# breakout.net
KiCad netlist of a schematic drawn in EAGLE
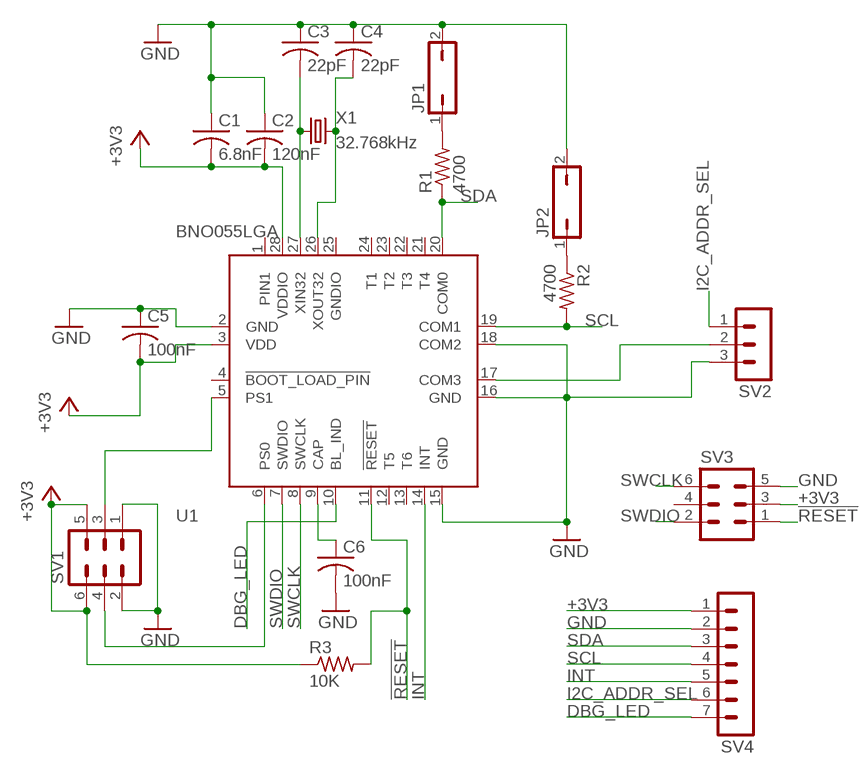
[diagram p0: schematic, sheet 1]

(export (version "E")
  (design (tool "Eeschema 10.0.6"))
  (components
    (comp (ref "C1")
      (value "6.8nF")
      (footprint "eagle-import:C0805")
      (libsource (lib "eagle-import") (part "C-USC0805"))
    )
    (comp (ref "C2")
      (value "120nF")
      (footprint "eagle-import:C0805")
      (libsource (lib "eagle-import") (part "C-USC0805"))
    )
    (comp (ref "C3")
      (value "22pF")
      (footprint "eagle-import:C0805")
      (libsource (lib "eagle-import") (part "C-USC0805"))
    )
    (comp (ref "C4")
      (value "22pF")
      (footprint "eagle-import:C0805")
      (libsource (lib "eagle-import") (part "C-USC0805"))
    )
    (comp (ref "C5")
      (value "100nF")
      (footprint "eagle-import:C0805")
      (libsource (lib "eagle-import") (part "C-USC0805"))
    )
    (comp (ref "C6")
      (value "100nF")
      (footprint "eagle-import:C0805")
      (libsource (lib "eagle-import") (part "C-USC0805"))
    )
    (comp (ref "JP1")
      (value "JP1Q")
      (footprint "eagle-import:JP1")
      (libsource (lib "eagle-import") (part "JP1Q"))
    )
    (comp (ref "JP2")
      (value "JP1Q")
      (footprint "eagle-import:JP1")
      (libsource (lib "eagle-import") (part "JP1Q"))
    )
    (comp (ref "R1")
      (value "4700")
      (footprint "eagle-import:R0805")
      (libsource (lib "eagle-import") (part "R-US_R0805"))
    )
    (comp (ref "R2")
      (value "4700")
      (footprint "eagle-import:R0805")
      (libsource (lib "eagle-import") (part "R-US_R0805"))
    )
    (comp (ref "R3")
      (value "10K")
      (footprint "eagle-import:R0805")
      (libsource (lib "eagle-import") (part "R-US_R0805"))
    )
    (comp (ref "SV1")
      (value "MA03-2")
      (footprint "eagle-import:MA03-2")
      (libsource (lib "eagle-import") (part "MA03-2"))
    )
    (comp (ref "SV2")
      (value "MA03-1")
      (footprint "eagle-import:MA03-1")
      (libsource (lib "eagle-import") (part "MA03-1"))
    )
    (comp (ref "SV3")
      (value "MA03-2")
      (footprint "eagle-import:MA03-2")
      (libsource (lib "eagle-import") (part "MA03-2"))
    )
    (comp (ref "SV4")
      (value "MA07-1")
      (footprint "eagle-import:MA07-1")
      (libsource (lib "eagle-import") (part "MA07-1"))
    )
    (comp (ref "U1")
      (value "BNO055LGA")
      (footprint "eagle-import:LGA28_BOSCH")
      (libsource (lib "eagle-import") (part "BNO055LGA"))
    )
    (comp (ref "X1")
      (value "32.768kHz")
      (footprint "eagle-import:WATCH-3X8")
      (libsource (lib "eagle-import") (part "CRYSTALS-NOGND-WATCH-3X8"))
    )
  )
  (nets
    (net (code "1") (name "+3V3") (class "Default")
      (node (ref "C1") (pin "2") (pinfunction "2_2") (pintype "passive"))
      (node (ref "C2") (pin "2") (pinfunction "2_2") (pintype "passive"))
      (node (ref "C5") (pin "2") (pinfunction "2_2") (pintype "passive"))
      (node (ref "R3") (pin "1") (pinfunction "1_1") (pintype "passive"))
      (node (ref "SV1") (pin "5") (pinfunction "5_5") (pintype "passive"))
      (node (ref "SV1") (pin "6") (pinfunction "6_6") (pintype "passive"))
      (node (ref "SV3") (pin "3") (pinfunction "3_3") (pintype "passive"))
      (node (ref "SV4") (pin "1") (pinfunction "1_1") (pintype "passive"))
      (node (ref "U1") (pin "28") (pinfunction "VDDIO_28") (pintype "power_in"))
      (node (ref "U1") (pin "3") (pinfunction "VDD_3") (pintype "power_in"))
    )
    (net (code "2") (name "/DBG_LED") (class "Default")
      (node (ref "SV4") (pin "7") (pinfunction "7_7") (pintype "passive"))
      (node (ref "U1") (pin "10") (pinfunction "BL_IND_10") (pintype "output"))
    )
    (net (code "3") (name "/GNDIO") (class "Default")
      (node (ref "U1") (pin "25") (pinfunction "GNDIO_25") (pintype "power_in"))
    )
    (net (code "4") (name "/I2C_ADDR_SEL") (class "Default")
      (node (ref "SV2") (pin "1") (pinfunction "1_1") (pintype "passive"))
      (node (ref "SV4") (pin "6") (pinfunction "6_6") (pintype "passive"))
    )
    (net (code "5") (name "/INT") (class "Default")
      (node (ref "SV4") (pin "5") (pinfunction "5_5") (pintype "passive"))
      (node (ref "U1") (pin "14") (pinfunction "INT_14") (pintype "output"))
    )
    (net (code "6") (name "/SCL") (class "Default")
      (node (ref "R2") (pin "2") (pinfunction "2_2") (pintype "passive"))
      (node (ref "SV4") (pin "4") (pinfunction "4_4") (pintype "passive"))
      (node (ref "U1") (pin "19") (pinfunction "COM1_19") (pintype "bidirectional"))
    )
    (net (code "7") (name "/SDA") (class "Default")
      (node (ref "R1") (pin "1") (pinfunction "1_1") (pintype "passive"))
      (node (ref "SV4") (pin "3") (pinfunction "3_3") (pintype "passive"))
      (node (ref "U1") (pin "20") (pinfunction "COM0_20") (pintype "bidirectional"))
    )
    (net (code "8") (name "/SWCLK") (class "Default")
      (node (ref "SV3") (pin "6") (pinfunction "6_6") (pintype "passive"))
      (node (ref "U1") (pin "8") (pinfunction "SWCLK_8") (pintype "bidirectional"))
    )
    (net (code "9") (name "/SWDIO") (class "Default")
      (node (ref "SV3") (pin "2") (pinfunction "2_2") (pintype "passive"))
      (node (ref "U1") (pin "7") (pinfunction "SWDIO_7") (pintype "bidirectional"))
    )
    (net (code "10") (name "/~{RESET}") (class "Default")
      (node (ref "R3") (pin "2") (pinfunction "2_2") (pintype "passive"))
      (node (ref "SV3") (pin "1") (pinfunction "1_1") (pintype "passive"))
      (node (ref "U1") (pin "11") (pinfunction "~{RESET}_11") (pintype "bidirectional"))
    )
    (net (code "11") (name "GND") (class "Default")
      (node (ref "C1") (pin "1") (pinfunction "1_1") (pintype "passive"))
      (node (ref "C2") (pin "1") (pinfunction "1_1") (pintype "passive"))
      (node (ref "C3") (pin "1") (pinfunction "1_1") (pintype "passive"))
      (node (ref "C4") (pin "1") (pinfunction "1_1") (pintype "passive"))
      (node (ref "C5") (pin "1") (pinfunction "1_1") (pintype "passive"))
      (node (ref "C6") (pin "2") (pinfunction "2_2") (pintype "passive"))
      (node (ref "JP1") (pin "2") (pinfunction "2_2") (pintype "passive"))
      (node (ref "JP2") (pin "2") (pinfunction "2_2") (pintype "passive"))
      (node (ref "SV1") (pin "1") (pinfunction "1_1") (pintype "passive"))
      (node (ref "SV1") (pin "2") (pinfunction "2_2") (pintype "passive"))
      (node (ref "SV2") (pin "3") (pinfunction "3_3") (pintype "passive"))
      (node (ref "SV3") (pin "5") (pinfunction "5_5") (pintype "passive"))
      (node (ref "SV4") (pin "2") (pinfunction "2_2") (pintype "passive"))
      (node (ref "U1") (pin "15") (pinfunction "GND_15") (pintype "power_in"))
      (node (ref "U1") (pin "16") (pinfunction "GND_16") (pintype "power_in"))
      (node (ref "U1") (pin "18") (pinfunction "COM2_18") (pintype "bidirectional"))
      (node (ref "U1") (pin "2") (pinfunction "GND_2") (pintype "power_in"))
    )
    (net (code "12") (name "Net-(JP1-Pad1)") (class "Default")
      (node (ref "JP1") (pin "1") (pinfunction "1_1") (pintype "passive"))
      (node (ref "R1") (pin "2") (pinfunction "2_2") (pintype "passive"))
    )
    (net (code "13") (name "Net-(JP2-Pad1)") (class "Default")
      (node (ref "JP2") (pin "1") (pinfunction "1_1") (pintype "passive"))
      (node (ref "R2") (pin "1") (pinfunction "1_1") (pintype "passive"))
    )
    (net (code "14") (name "Net-(U1-CAP)") (class "Default")
      (node (ref "C6") (pin "1") (pinfunction "1_1") (pintype "passive"))
      (node (ref "U1") (pin "9") (pinfunction "CAP_9") (pintype "bidirectional"))
    )
    (net (code "15") (name "Net-(U1-COM3)") (class "Default")
      (node (ref "SV2") (pin "2") (pinfunction "2_2") (pintype "passive"))
      (node (ref "U1") (pin "17") (pinfunction "COM3_17") (pintype "input"))
    )
    (net (code "16") (name "Net-(U1-PS0)") (class "Default")
      (node (ref "SV1") (pin "4") (pinfunction "4_4") (pintype "passive"))
      (node (ref "U1") (pin "6") (pinfunction "PS0_6") (pintype "input"))
    )
    (net (code "17") (name "Net-(U1-PS1)") (class "Default")
      (node (ref "SV1") (pin "3") (pinfunction "3_3") (pintype "passive"))
      (node (ref "U1") (pin "5") (pinfunction "PS1_5") (pintype "input"))
    )
    (net (code "18") (name "Net-(U1-XIN32)") (class "Default")
      (node (ref "C3") (pin "2") (pinfunction "2_2") (pintype "passive"))
      (node (ref "U1") (pin "27") (pinfunction "XIN32_27") (pintype "input"))
      (node (ref "X1") (pin "1") (pinfunction "1_1") (pintype "passive"))
    )
    (net (code "19") (name "Net-(U1-XOUT32)") (class "Default")
      (node (ref "C4") (pin "2") (pinfunction "2_2") (pintype "passive"))
      (node (ref "U1") (pin "26") (pinfunction "XOUT32_26") (pintype "output"))
      (node (ref "X1") (pin "2") (pinfunction "2_2") (pintype "passive"))
    )
    (net (code "20") (name "unconnected-(SV3-Pad4)") (class "Default")
      (node (ref "SV3") (pin "4") (pinfunction "4_4") (pintype "passive"))
    )
    (net (code "21") (name "unconnected-(U1-PIN1-Pad1)") (class "Default")
      (node (ref "U1") (pin "1") (pinfunction "PIN1_1") (pintype "no_connect"))
    )
    (net (code "22") (name "unconnected-(U1-T1-Pad24)") (class "Default")
      (node (ref "U1") (pin "24") (pinfunction "T1_24") (pintype "no_connect"))
    )
    (net (code "23") (name "unconnected-(U1-T2-Pad23)") (class "Default")
      (node (ref "U1") (pin "23") (pinfunction "T2_23") (pintype "no_connect"))
    )
    (net (code "24") (name "unconnected-(U1-T3-Pad22)") (class "Default")
      (node (ref "U1") (pin "22") (pinfunction "T3_22") (pintype "no_connect"))
    )
    (net (code "25") (name "unconnected-(U1-T4-Pad21)") (class "Default")
      (node (ref "U1") (pin "21") (pinfunction "T4_21") (pintype "no_connect"))
    )
    (net (code "26") (name "unconnected-(U1-T5-Pad12)") (class "Default")
      (node (ref "U1") (pin "12") (pinfunction "T5_12") (pintype "no_connect"))
    )
    (net (code "27") (name "unconnected-(U1-T6-Pad13)") (class "Default")
      (node (ref "U1") (pin "13") (pinfunction "T6_13") (pintype "no_connect"))
    )
    (net (code "28") (name "unconnected-(U1-~{BOOT_LOAD_PIN}-Pad4)") (class "Default")
      (node (ref "U1") (pin "4") (pinfunction "~{BOOT_LOAD_PIN}_4") (pintype "input"))
    )
  )
)
